# Printrhub_Rev_0_1.net
KiCad netlist of a schematic drawn in EAGLE
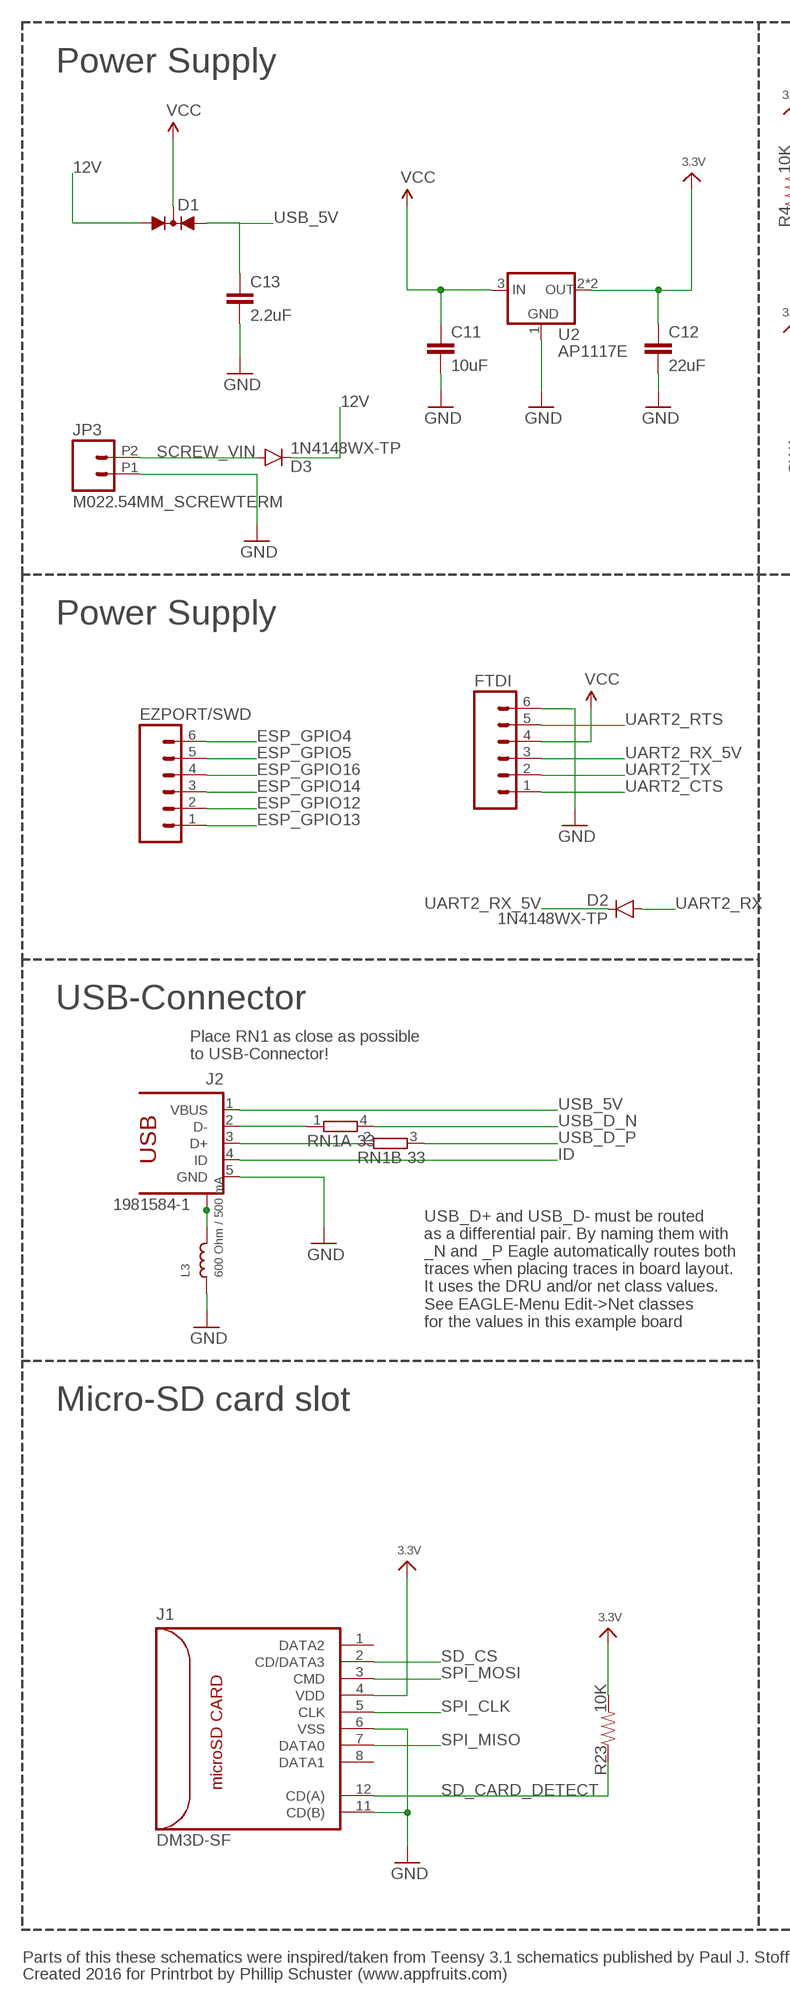
[diagram p0: schematic, sheet 1, part 1 of 2]
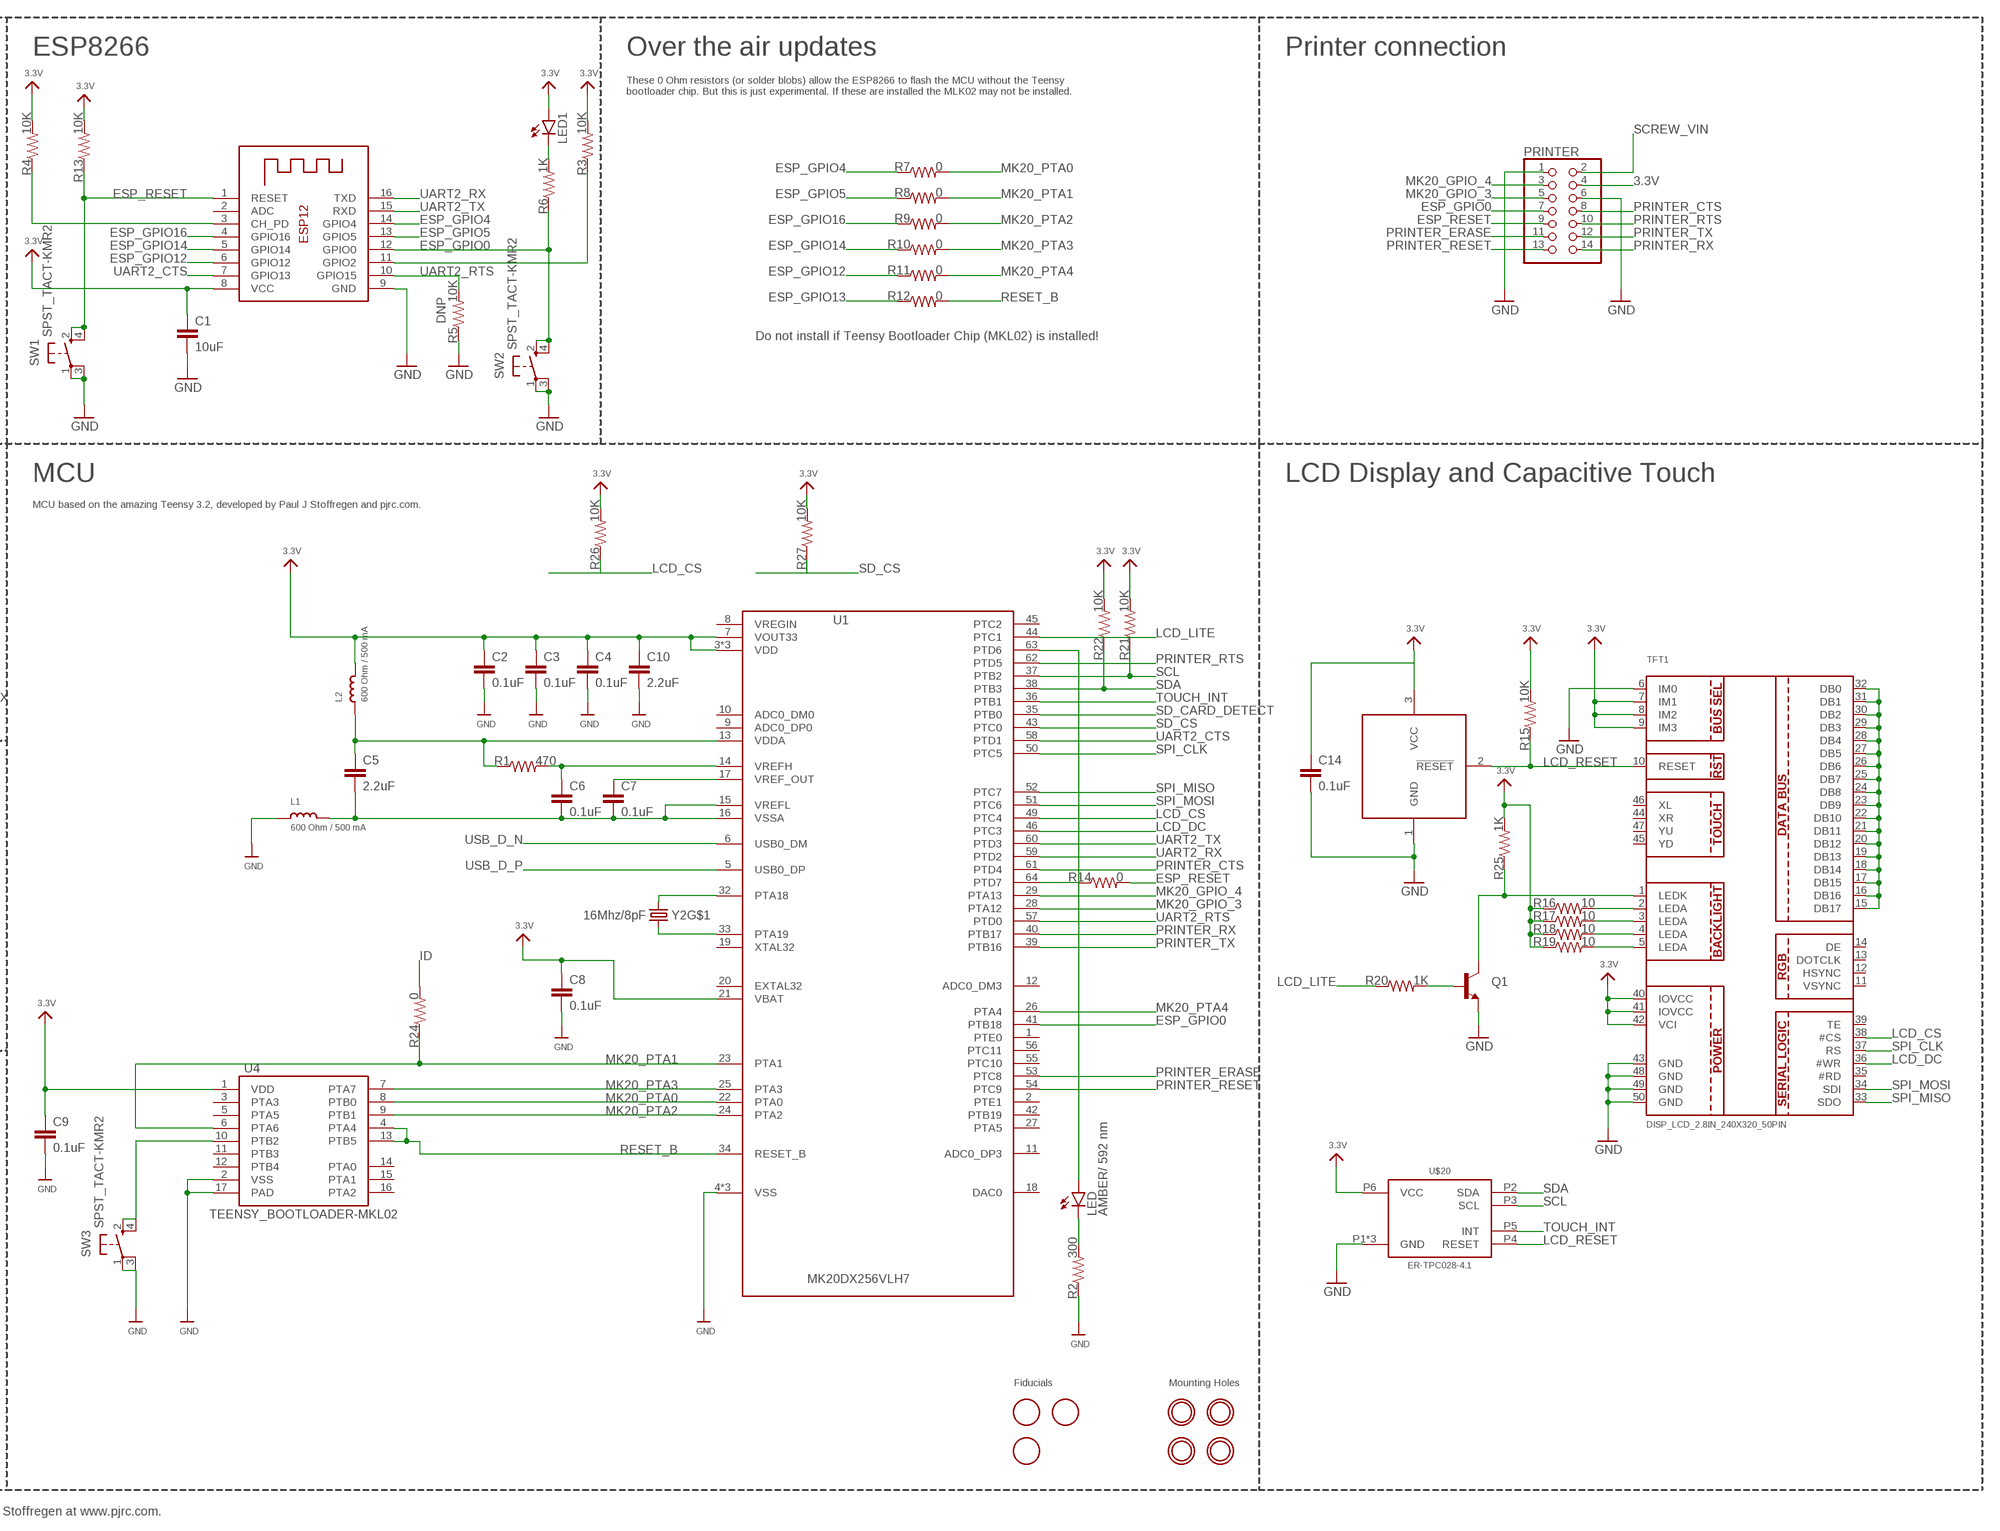
[diagram p1: schematic, sheet 1, part 2 of 2]

(export (version "E")
  (design (tool "Eeschema 10.0.6"))
  (components
    (comp (ref "C1")
      (value "10uF")
      (footprint "eagle-import:0603-CAP")
      (fields (field (name "MF") "Murata") (field (name "MPN") "GRM188R60J106ME47D"))
      (libsource (lib "eagle-import") (part "CAPACITOR-10UF"))
    )
    (comp (ref "C2")
      (value "0.1uF")
      (footprint "eagle-import:0603-CAP")
      (fields (field (name "MF") "Kemet") (field (name "MPN") "C0603C104J3RACTU"))
      (libsource (lib "eagle-import") (part "CAPACITOR-0.1UF"))
    )
    (comp (ref "C3")
      (value "0.1uF")
      (footprint "eagle-import:0603-CAP")
      (fields (field (name "MF") "Kemet") (field (name "MPN") "C0603C104J3RACTU"))
      (libsource (lib "eagle-import") (part "CAPACITOR-0.1UF"))
    )
    (comp (ref "C4")
      (value "0.1uF")
      (footprint "eagle-import:0603-CAP")
      (fields (field (name "MF") "Kemet") (field (name "MPN") "C0603C104J3RACTU"))
      (libsource (lib "eagle-import") (part "CAPACITOR-0.1UF"))
    )
    (comp (ref "C5")
      (value "2.2uF")
      (footprint "eagle-import:0603-CAP")
      (fields (field (name "MF") "Kemet") (field (name "MPN") "C0603C225K4PACTU"))
      (libsource (lib "eagle-import") (part "CAPACITOR-2.2UF"))
    )
    (comp (ref "C6")
      (value "0.1uF")
      (footprint "eagle-import:0603-CAP")
      (fields (field (name "MF") "Kemet") (field (name "MPN") "C0603C104J3RACTU"))
      (libsource (lib "eagle-import") (part "CAPACITOR-0.1UF"))
    )
    (comp (ref "C7")
      (value "0.1uF")
      (footprint "eagle-import:0603-CAP")
      (fields (field (name "MF") "Kemet") (field (name "MPN") "C0603C104J3RACTU"))
      (libsource (lib "eagle-import") (part "CAPACITOR-0.1UF"))
    )
    (comp (ref "C8")
      (value "0.1uF")
      (footprint "eagle-import:0603-CAP")
      (fields (field (name "MF") "Kemet") (field (name "MPN") "C0603C104J3RACTU"))
      (libsource (lib "eagle-import") (part "CAPACITOR-0.1UF"))
    )
    (comp (ref "C9")
      (value "0.1uF")
      (footprint "eagle-import:0603-CAP")
      (fields (field (name "MF") "Kemet") (field (name "MPN") "C0603C104J3RACTU"))
      (libsource (lib "eagle-import") (part "CAPACITOR-0.1UF"))
    )
    (comp (ref "C10")
      (value "2.2uF")
      (footprint "eagle-import:0603-CAP")
      (fields (field (name "MF") "Kemet") (field (name "MPN") "C0603C225K4PACTU"))
      (libsource (lib "eagle-import") (part "CAPACITOR-2.2UF"))
    )
    (comp (ref "C11")
      (value "10uF")
      (footprint "eagle-import:0603-CAP")
      (fields (field (name "MF") "Murata") (field (name "MPN") "GRM188R60J106ME47D"))
      (libsource (lib "eagle-import") (part "CAPACITOR-10UF"))
    )
    (comp (ref "C12")
      (value "22uF")
      (footprint "eagle-import:0603-CAP")
      (fields (field (name "MF") "Murata") (field (name "MPN") "GRM188R60J226MEA0D"))
      (libsource (lib "eagle-import") (part "CAPACITOR-22UF"))
    )
    (comp (ref "C13")
      (value "2.2uF")
      (footprint "eagle-import:0603-CAP")
      (fields (field (name "MF") "Kemet") (field (name "MPN") "C0603C225K4PACTU"))
      (libsource (lib "eagle-import") (part "CAPACITOR-2.2UF"))
    )
    (comp (ref "C14")
      (value "0.1uF")
      (footprint "eagle-import:0603-CAP")
      (fields (field (name "MF") "Kemet") (field (name "MPN") "C0603C104J3RACTU"))
      (libsource (lib "eagle-import") (part "CAPACITOR-0.1UF"))
    )
    (comp (ref "D1")
      (value "DIODE-2AC|CASOT23")
      (footprint "eagle-import:SOT23")
      (libsource (lib "eagle-import") (part "DIODE-2AC|CASOT23"))
    )
    (comp (ref "D2")
      (value "1N4148WX-TP")
      (footprint "eagle-import:SOD-323")
      (fields (field (name "MF") "Micro Commercial Co"))
      (libsource (lib "eagle-import") (part "DIODESOD"))
    )
    (comp (ref "D3")
      (value "1N4148WX-TP")
      (footprint "eagle-import:SOD-323")
      (fields (field (name "MF") "Micro Commercial Co"))
      (libsource (lib "eagle-import") (part "DIODESOD"))
    )
    (comp (ref "EZPORT/SWD")
      (value "M06SMD-STRAIGHT")
      (footprint "eagle-import:1X06_SMD_STRAIGHT")
      (libsource (lib "eagle-import") (part "M06SMD-STRAIGHT"))
    )
    (comp (ref "FTDI")
      (value "M06SMD-STRAIGHT")
      (footprint "eagle-import:1X06_SMD_STRAIGHT")
      (libsource (lib "eagle-import") (part "M06SMD-STRAIGHT"))
    )
    (comp (ref "J1")
      (value "DM3D-SF")
      (footprint "eagle-import:DM3D-SF")
      (libsource (lib "eagle-import") (part "DM3D-SF"))
    )
    (comp (ref "J2")
      (value "1981584-1")
      (footprint "eagle-import:1981584-1")
      (libsource (lib "eagle-import") (part "1981584-1"))
    )
    (comp (ref "JP3")
      (value "M022.54MM_SCREWTERM")
      (footprint "eagle-import:1X02_2.54_SCREWTERM")
      (libsource (lib "eagle-import") (part "M022.54MM_SCREWTERM"))
    )
    (comp (ref "L1")
      (value "600 Ohm / 500 mA")
      (footprint "eagle-import:0603")
      (fields (field (name "MF") "Murata") (field (name "MPN") "BLM18AG601SN1D"))
      (libsource (lib "eagle-import") (part "INDUCTOR-0603_600OHM/500MA"))
    )
    (comp (ref "L2")
      (value "600 Ohm / 500 mA")
      (footprint "eagle-import:0603")
      (fields (field (name "MF") "Murata") (field (name "MPN") "BLM18AG601SN1D"))
      (libsource (lib "eagle-import") (part "INDUCTOR-0603_600OHM/500MA"))
    )
    (comp (ref "L3")
      (value "600 Ohm / 500 mA")
      (footprint "eagle-import:0603")
      (fields (field (name "MF") "Murata") (field (name "MPN") "BLM18AG601SN1D"))
      (libsource (lib "eagle-import") (part "INDUCTOR-0603_600OHM/500MA"))
    )
    (comp (ref "LED")
      (value "AMBER/ 592 nm")
      (footprint "eagle-import:LED-0603")
      (fields (field (name "MF") "Avago Technologies") (field (name "MPN") "HSMA-C190"))
      (libsource (lib "eagle-import") (part "LED-AMBER"))
    )
    (comp (ref "LED1")
      (value "LED-GREEN")
      (footprint "eagle-import:LED-0603")
      (fields (field (name "MF") "Avago") (field (name "MPN") "HSMG-C190"))
      (libsource (lib "eagle-import") (part "LED-GREEN"))
    )
    (comp (ref "PRINTER")
      (value "PINHD-2X7SMT")
      (footprint "eagle-import:2X07_SMT")
      (libsource (lib "eagle-import") (part "PINHD-2X7SMT"))
    )
    (comp (ref "Q1")
      (value "TRANSISTOR_NPNSOT23-3")
      (footprint "eagle-import:SOT23-3")
      (fields (field (name "MF") "ON Semiconductor") (field (name "MPN") "MMBT2222ALT1G"))
      (libsource (lib "eagle-import") (part "TRANSISTOR_NPNSOT23-3"))
    )
    (comp (ref "R1")
      (value "470")
      (footprint "eagle-import:0603-RES")
      (fields (field (name "MF") "Panasonic") (field (name "MPN") "ERJ-3GEYJ471V"))
      (libsource (lib "eagle-import") (part "RESISTOR-470"))
    )
    (comp (ref "R2")
      (value "300")
      (footprint "eagle-import:0603-RES")
      (libsource (lib "eagle-import") (part "RESISTOR0603"))
    )
    (comp (ref "R3")
      (value "10K")
      (footprint "eagle-import:0603-RES")
      (fields (field (name "MF") "Panasonic") (field (name "MPN") "ERJ-3GEYJ103V"))
      (libsource (lib "eagle-import") (part "RESISTOR-10K"))
    )
    (comp (ref "R4")
      (value "10K")
      (footprint "eagle-import:0603-RES")
      (fields (field (name "MF") "Panasonic") (field (name "MPN") "ERJ-3GEYJ103V"))
      (libsource (lib "eagle-import") (part "RESISTOR-10K"))
    )
    (comp (ref "R5")
      (value "10K")
      (footprint "eagle-import:0603-RES")
      (fields (field (name "MF") "Panasonic") (field (name "MPN") "ERJ-3GEYJ103V"))
      (libsource (lib "eagle-import") (part "RESISTOR-10K"))
    )
    (comp (ref "R6")
      (value "1K")
      (footprint "eagle-import:0603-RES")
      (fields (field (name "MF") "Panasonic") (field (name "MPN") "ERJ-3GEYJ102V"))
      (libsource (lib "eagle-import") (part "RESISTOR-1K"))
    )
    (comp (ref "R7")
      (value "0")
      (footprint "eagle-import:0603-RES")
      (fields (field (name "MF") "Panasonic") (field (name "MPN") "ERJ-3GEY0R00V"))
      (libsource (lib "eagle-import") (part "RESISTOR-0"))
    )
    (comp (ref "R8")
      (value "0")
      (footprint "eagle-import:0603-RES")
      (fields (field (name "MF") "Panasonic") (field (name "MPN") "ERJ-3GEY0R00V"))
      (libsource (lib "eagle-import") (part "RESISTOR-0"))
    )
    (comp (ref "R9")
      (value "0")
      (footprint "eagle-import:0603-RES")
      (fields (field (name "MF") "Panasonic") (field (name "MPN") "ERJ-3GEY0R00V"))
      (libsource (lib "eagle-import") (part "RESISTOR-0"))
    )
    (comp (ref "R10")
      (value "0")
      (footprint "eagle-import:0603-RES")
      (fields (field (name "MF") "Panasonic") (field (name "MPN") "ERJ-3GEY0R00V"))
      (libsource (lib "eagle-import") (part "RESISTOR-0"))
    )
    (comp (ref "R11")
      (value "0")
      (footprint "eagle-import:0603-RES")
      (fields (field (name "MF") "Panasonic") (field (name "MPN") "ERJ-3GEY0R00V"))
      (libsource (lib "eagle-import") (part "RESISTOR-0"))
    )
    (comp (ref "R12")
      (value "0")
      (footprint "eagle-import:0603-RES")
      (fields (field (name "MF") "Panasonic") (field (name "MPN") "ERJ-3GEY0R00V"))
      (libsource (lib "eagle-import") (part "RESISTOR-0"))
    )
    (comp (ref "R13")
      (value "10K")
      (footprint "eagle-import:0603-RES")
      (fields (field (name "MF") "Panasonic") (field (name "MPN") "ERJ-3GEYJ103V"))
      (libsource (lib "eagle-import") (part "RESISTOR-10K"))
    )
    (comp (ref "R14")
      (value "0")
      (footprint "eagle-import:0603-RES")
      (fields (field (name "MF") "Panasonic") (field (name "MPN") "ERJ-3GEY0R00V"))
      (libsource (lib "eagle-import") (part "RESISTOR-0"))
    )
    (comp (ref "R15")
      (value "10K")
      (footprint "eagle-import:0603-RES")
      (fields (field (name "MF") "Panasonic") (field (name "MPN") "ERJ-3GEYJ103V"))
      (libsource (lib "eagle-import") (part "RESISTOR-10K"))
    )
    (comp (ref "R16")
      (value "10")
      (footprint "eagle-import:0603-RES")
      (fields (field (name "MF") "Panasonic") (field (name "MPN") "ERJ-3EKF10R0V"))
      (libsource (lib "eagle-import") (part "RESISTOR-10"))
    )
    (comp (ref "R17")
      (value "10")
      (footprint "eagle-import:0603-RES")
      (fields (field (name "MF") "Panasonic") (field (name "MPN") "ERJ-3EKF10R0V"))
      (libsource (lib "eagle-import") (part "RESISTOR-10"))
    )
    (comp (ref "R18")
      (value "10")
      (footprint "eagle-import:0603-RES")
      (fields (field (name "MF") "Panasonic") (field (name "MPN") "ERJ-3EKF10R0V"))
      (libsource (lib "eagle-import") (part "RESISTOR-10"))
    )
    (comp (ref "R19")
      (value "10")
      (footprint "eagle-import:0603-RES")
      (fields (field (name "MF") "Panasonic") (field (name "MPN") "ERJ-3EKF10R0V"))
      (libsource (lib "eagle-import") (part "RESISTOR-10"))
    )
    (comp (ref "R20")
      (value "1K")
      (footprint "eagle-import:0603-RES")
      (fields (field (name "MF") "Panasonic") (field (name "MPN") "ERJ-3GEYJ102V"))
      (libsource (lib "eagle-import") (part "RESISTOR-1K"))
    )
    (comp (ref "R21")
      (value "10K")
      (footprint "eagle-import:0603-RES")
      (fields (field (name "MF") "Panasonic") (field (name "MPN") "ERJ-3GEYJ103V"))
      (libsource (lib "eagle-import") (part "RESISTOR-10K"))
    )
    (comp (ref "R22")
      (value "10K")
      (footprint "eagle-import:0603-RES")
      (fields (field (name "MF") "Panasonic") (field (name "MPN") "ERJ-3GEYJ103V"))
      (libsource (lib "eagle-import") (part "RESISTOR-10K"))
    )
    (comp (ref "R23")
      (value "10K")
      (footprint "eagle-import:0603-RES")
      (fields (field (name "MF") "Panasonic") (field (name "MPN") "ERJ-3GEYJ103V"))
      (libsource (lib "eagle-import") (part "RESISTOR-10K"))
    )
    (comp (ref "R24")
      (value "0")
      (footprint "eagle-import:0603-RES")
      (fields (field (name "MF") "Panasonic") (field (name "MPN") "ERJ-3GEY0R00V"))
      (libsource (lib "eagle-import") (part "RESISTOR-0"))
    )
    (comp (ref "R25")
      (value "1K")
      (footprint "eagle-import:0603-RES")
      (fields (field (name "MF") "Panasonic") (field (name "MPN") "ERJ-3GEYJ102V"))
      (libsource (lib "eagle-import") (part "RESISTOR-1K"))
    )
    (comp (ref "R26")
      (value "10K")
      (footprint "eagle-import:0603-RES")
      (fields (field (name "MF") "Panasonic") (field (name "MPN") "ERJ-3GEYJ103V"))
      (libsource (lib "eagle-import") (part "RESISTOR-10K"))
    )
    (comp (ref "R27")
      (value "10K")
      (footprint "eagle-import:0603-RES")
      (fields (field (name "MF") "Panasonic") (field (name "MPN") "ERJ-3GEYJ103V"))
      (libsource (lib "eagle-import") (part "RESISTOR-10K"))
    )
    (comp (ref "RN1")
      (value "33")
      (footprint "eagle-import:EXB34V")
      (fields (field (name "MF") "Panasonic") (field (name "MPN") "EXB-34V330JV"))
      (libsource (lib "eagle-import") (part "2R-NEXB34V"))
    )
    (comp (ref "SW1")
      (value "SPST_TACT-KMR2")
      (footprint "eagle-import:KMR2")
      (libsource (lib "eagle-import") (part "SPST_TACT-KMR2"))
    )
    (comp (ref "SW2")
      (value "SPST_TACT-KMR2")
      (footprint "eagle-import:KMR2")
      (libsource (lib "eagle-import") (part "SPST_TACT-KMR2"))
    )
    (comp (ref "SW3")
      (value "SPST_TACT-KMR2")
      (footprint "eagle-import:KMR2")
      (libsource (lib "eagle-import") (part "SPST_TACT-KMR2"))
    )
    (comp (ref "TFT1")
      (value "DISP_LCD_2.8IN_240X320_50PIN")
      (footprint "eagle-import:TFT_2.83IN_240X320_50PIN")
      (libsource (lib "eagle-import") (part "DISP_LCD_2.8IN_240X320_50PIN"))
    )
    (comp (ref "U$15")
      (value "MOUNTINGHOLE2.0")
      (footprint "eagle-import:MOUNTINGHOLE_2.0_PLATED")
      (libsource (lib "eagle-import") (part "MOUNTINGHOLE2.0"))
    )
    (comp (ref "U$16")
      (value "MOUNTINGHOLE2.0")
      (footprint "eagle-import:MOUNTINGHOLE_2.0_PLATED")
      (libsource (lib "eagle-import") (part "MOUNTINGHOLE2.0"))
    )
    (comp (ref "U$17")
      (value "MOUNTINGHOLE2.0")
      (footprint "eagle-import:MOUNTINGHOLE_2.0_PLATED")
      (libsource (lib "eagle-import") (part "MOUNTINGHOLE2.0"))
    )
    (comp (ref "U$18")
      (value "MOUNTINGHOLE2.0")
      (footprint "eagle-import:MOUNTINGHOLE_2.0_PLATED")
      (libsource (lib "eagle-import") (part "MOUNTINGHOLE2.0"))
    )
    (comp (ref "U$20")
      (value "ER-TPC028-4.1")
      (footprint "eagle-import:ER-CON06HB-1")
      (libsource (lib "eagle-import") (part "ER-TPC028-4.1"))
    )
    (comp (ref "U$38")
      (value "FIDUCIAL")
      (footprint "eagle-import:FIDUCIAL_1MM")
      (libsource (lib "eagle-import") (part "FIDUCIAL"))
    )
    (comp (ref "U$39")
      (value "FIDUCIAL")
      (footprint "eagle-import:FIDUCIAL_1MM")
      (libsource (lib "eagle-import") (part "FIDUCIAL"))
    )
    (comp (ref "U$40")
      (value "FIDUCIAL")
      (footprint "eagle-import:FIDUCIAL_1MM")
      (libsource (lib "eagle-import") (part "FIDUCIAL"))
    )
    (comp (ref "U1")
      (value "MK20DX256VLH7")
      (footprint "eagle-import:MK20DX256VLH7")
      (fields (field (name "MF") "Freescale"))
      (libsource (lib "eagle-import") (part "MK20DX256VLH7"))
    )
    (comp (ref "U2")
      (value "AP1117E")
      (footprint "eagle-import:SOT223")
      (libsource (lib "eagle-import") (part "AP1117E"))
    )
    (comp (ref "U3")
      (value "MAX308-SOT23")
      (footprint "eagle-import:SOT23")
      (libsource (lib "eagle-import") (part "MAX308-SOT23"))
    )
    (comp (ref "U4")
      (value "TEENSY_BOOTLOADER-MKL02")
      (footprint "eagle-import:QFN50P300X300X100-17N")
      (libsource (lib "eagle-import") (part "TEENSY_BOOTLOADER-MKL02"))
    )
    (comp (ref "X1")
      (value "ESP-12")
      (footprint "eagle-import:ESP-12")
      (libsource (lib "eagle-import") (part "ESP-12"))
    )
    (comp (ref "Y2")
      (value "16Mhz/8pF")
      (footprint "eagle-import:CRYSTAL-SMD-5X3")
      (fields (field (name "MF") "ECS") (field (name "MPN") "ECS-160-8-30B-CKM"))
      (libsource (lib "eagle-import") (part "CRYSTAL/SMD-5X3-GND16MHZ/8PF"))
    )
  )
  (nets
    (net (code "1") (name "/12V") (class "Default")
      (node (ref "D1") (pin "1") (pinfunction "A1_1") (pintype "passive"))
      (node (ref "D3") (pin "C") (pinfunction "C_C") (pintype "passive"))
    )
    (net (code "2") (name "/ESP_GPIO0") (class "Default")
      (node (ref "PRINTER") (pin "7") (pinfunction "7_7") (pintype "passive"))
      (node (ref "R6") (pin "1") (pinfunction "1_1") (pintype "passive"))
      (node (ref "SW2") (pin "2") (pinfunction "S_2") (pintype "passive"))
      (node (ref "SW2") (pin "4") (pinfunction "S1_4") (pintype "passive"))
      (node (ref "U1") (pin "41") (pinfunction "PTB18_41") (pintype "bidirectional"))
      (node (ref "X1") (pin "12") (pinfunction "GPIO0_12") (pintype "bidirectional"))
    )
    (net (code "3") (name "/ESP_GPIO4") (class "Default")
      (node (ref "EZPORT/SWD") (pin "6") (pinfunction "6_6") (pintype "passive"))
      (node (ref "R7") (pin "1") (pinfunction "1_1") (pintype "passive"))
      (node (ref "X1") (pin "14") (pinfunction "GPIO4_14") (pintype "bidirectional"))
    )
    (net (code "4") (name "/ESP_GPIO5") (class "Default")
      (node (ref "EZPORT/SWD") (pin "5") (pinfunction "5_5") (pintype "passive"))
      (node (ref "R8") (pin "1") (pinfunction "1_1") (pintype "passive"))
      (node (ref "X1") (pin "13") (pinfunction "GPIO5_13") (pintype "bidirectional"))
    )
    (net (code "5") (name "/ESP_GPIO12") (class "Default")
      (node (ref "EZPORT/SWD") (pin "2") (pinfunction "2_2") (pintype "passive"))
      (node (ref "R11") (pin "1") (pinfunction "1_1") (pintype "passive"))
      (node (ref "X1") (pin "6") (pinfunction "GPIO12_6") (pintype "bidirectional"))
    )
    (net (code "6") (name "/ESP_GPIO13") (class "Default")
      (node (ref "EZPORT/SWD") (pin "1") (pinfunction "1_1") (pintype "passive"))
      (node (ref "R12") (pin "1") (pinfunction "1_1") (pintype "passive"))
    )
    (net (code "7") (name "/ESP_GPIO14") (class "Default")
      (node (ref "EZPORT/SWD") (pin "3") (pinfunction "3_3") (pintype "passive"))
      (node (ref "R10") (pin "1") (pinfunction "1_1") (pintype "passive"))
      (node (ref "X1") (pin "5") (pinfunction "GPIO14_5") (pintype "bidirectional"))
    )
    (net (code "8") (name "/ESP_GPIO16") (class "Default")
      (node (ref "EZPORT/SWD") (pin "4") (pinfunction "4_4") (pintype "passive"))
      (node (ref "R9") (pin "1") (pinfunction "1_1") (pintype "passive"))
      (node (ref "X1") (pin "4") (pinfunction "GPIO16_4") (pintype "bidirectional"))
    )
    (net (code "9") (name "/ESP_RESET") (class "Default")
      (node (ref "PRINTER") (pin "9") (pinfunction "9_9") (pintype "passive"))
      (node (ref "R13") (pin "1") (pinfunction "1_1") (pintype "passive"))
      (node (ref "R14") (pin "2") (pinfunction "2_2") (pintype "passive"))
      (node (ref "SW1") (pin "2") (pinfunction "S_2") (pintype "passive"))
      (node (ref "SW1") (pin "4") (pinfunction "S1_4") (pintype "passive"))
      (node (ref "X1") (pin "1") (pinfunction "RESET_1") (pintype "input"))
    )
    (net (code "10") (name "/ID") (class "Default")
      (node (ref "J2") (pin "4") (pinfunction "ID_4") (pintype "passive"))
      (node (ref "R24") (pin "2") (pinfunction "2_2") (pintype "passive"))
    )
    (net (code "11") (name "/LCD_CS") (class "Default")
      (node (ref "R26") (pin "1") (pinfunction "1_1") (pintype "passive"))
      (node (ref "TFT1") (pin "38") (pinfunction "#CS_38") (pintype "bidirectional"))
      (node (ref "U1") (pin "49") (pinfunction "PTC4_49") (pintype "bidirectional"))
    )
    (net (code "12") (name "/LCD_DC") (class "Default")
      (node (ref "TFT1") (pin "36") (pinfunction "#WR_36") (pintype "bidirectional"))
      (node (ref "U1") (pin "46") (pinfunction "PTC3_46") (pintype "bidirectional"))
    )
    (net (code "13") (name "/LCD_LITE") (class "Default")
      (node (ref "R20") (pin "1") (pinfunction "1_1") (pintype "passive"))
      (node (ref "U1") (pin "44") (pinfunction "PTC1_44") (pintype "bidirectional"))
    )
    (net (code "14") (name "/LCD_RESET") (class "Default")
      (node (ref "R15") (pin "1") (pinfunction "1_1") (pintype "passive"))
      (node (ref "TFT1") (pin "10") (pinfunction "RESET_10") (pintype "bidirectional"))
      (node (ref "U$20") (pin "P4") (pinfunction "RESET_P4") (pintype "bidirectional"))
      (node (ref "U3") (pin "2") (pinfunction "~{RESET}_2") (pintype "bidirectional"))
    )
    (net (code "15") (name "/MK20_GPIO_3") (class "Default")
      (node (ref "PRINTER") (pin "5") (pinfunction "5_5") (pintype "passive"))
      (node (ref "U1") (pin "28") (pinfunction "PTA12_28") (pintype "bidirectional"))
    )
    (net (code "16") (name "/MK20_GPIO_4") (class "Default")
      (node (ref "PRINTER") (pin "3") (pinfunction "3_3") (pintype "passive"))
      (node (ref "U1") (pin "29") (pinfunction "PTA13_29") (pintype "bidirectional"))
    )
    (net (code "17") (name "/MK20_PTA0") (class "Default")
      (node (ref "R7") (pin "2") (pinfunction "2_2") (pintype "passive"))
      (node (ref "U1") (pin "22") (pinfunction "PTA0_22") (pintype "bidirectional"))
      (node (ref "U4") (pin "8") (pinfunction "PTB0_8") (pintype "bidirectional"))
    )
    (net (code "18") (name "/MK20_PTA1") (class "Default")
      (node (ref "R24") (pin "1") (pinfunction "1_1") (pintype "passive"))
      (node (ref "R8") (pin "2") (pinfunction "2_2") (pintype "passive"))
      (node (ref "U1") (pin "23") (pinfunction "PTA1_23") (pintype "bidirectional"))
      (node (ref "U4") (pin "6") (pinfunction "PTA6_6") (pintype "bidirectional"))
    )
    (net (code "19") (name "/MK20_PTA2") (class "Default")
      (node (ref "R9") (pin "2") (pinfunction "2_2") (pintype "passive"))
      (node (ref "U1") (pin "24") (pinfunction "PTA2_24") (pintype "bidirectional"))
      (node (ref "U4") (pin "9") (pinfunction "PTB1_9") (pintype "bidirectional"))
    )
    (net (code "20") (name "/MK20_PTA3") (class "Default")
      (node (ref "R10") (pin "2") (pinfunction "2_2") (pintype "passive"))
      (node (ref "U1") (pin "25") (pinfunction "PTA3_25") (pintype "bidirectional"))
      (node (ref "U4") (pin "7") (pinfunction "PTA7_7") (pintype "bidirectional"))
    )
    (net (code "21") (name "/MK20_PTA4") (class "Default")
      (node (ref "R11") (pin "2") (pinfunction "2_2") (pintype "passive"))
      (node (ref "U1") (pin "26") (pinfunction "PTA4_26") (pintype "bidirectional"))
    )
    (net (code "22") (name "/PRINTER_CTS") (class "Default")
      (node (ref "PRINTER") (pin "8") (pinfunction "8_8") (pintype "passive"))
      (node (ref "U1") (pin "61") (pinfunction "PTD4_61") (pintype "bidirectional"))
    )
    (net (code "23") (name "/PRINTER_ERASE") (class "Default")
      (node (ref "PRINTER") (pin "11") (pinfunction "11_11") (pintype "passive"))
      (node (ref "U1") (pin "53") (pinfunction "PTC8_53") (pintype "bidirectional"))
    )
    (net (code "24") (name "/PRINTER_RESET") (class "Default")
      (node (ref "PRINTER") (pin "13") (pinfunction "13_13") (pintype "passive"))
      (node (ref "U1") (pin "54") (pinfunction "PTC9_54") (pintype "bidirectional"))
    )
    (net (code "25") (name "/PRINTER_RTS") (class "Default")
      (node (ref "PRINTER") (pin "10") (pinfunction "10_10") (pintype "passive"))
      (node (ref "U1") (pin "62") (pinfunction "PTD5_62") (pintype "bidirectional"))
    )
    (net (code "26") (name "/PRINTER_RX") (class "Default")
      (node (ref "PRINTER") (pin "14") (pinfunction "14_14") (pintype "passive"))
      (node (ref "U1") (pin "40") (pinfunction "PTB17_40") (pintype "bidirectional"))
    )
    (net (code "27") (name "/PRINTER_TX") (class "Default")
      (node (ref "PRINTER") (pin "12") (pinfunction "12_12") (pintype "passive"))
      (node (ref "U1") (pin "39") (pinfunction "PTB16_39") (pintype "bidirectional"))
    )
    (net (code "28") (name "/RESET_B") (class "Default")
      (node (ref "R12") (pin "2") (pinfunction "2_2") (pintype "passive"))
      (node (ref "U1") (pin "34") (pinfunction "RESET_B_34") (pintype "bidirectional"))
      (node (ref "U4") (pin "13") (pinfunction "PTB5_13") (pintype "bidirectional"))
      (node (ref "U4") (pin "4") (pinfunction "PTA4_4") (pintype "bidirectional"))
    )
    (net (code "29") (name "/SCL") (class "Default")
      (node (ref "R21") (pin "1") (pinfunction "1_1") (pintype "passive"))
      (node (ref "U$20") (pin "P3") (pinfunction "SCL_P3") (pintype "bidirectional"))
      (node (ref "U1") (pin "37") (pinfunction "PTB2_37") (pintype "bidirectional"))
    )
    (net (code "30") (name "/SCREW_VIN") (class "Default")
      (node (ref "D3") (pin "A") (pinfunction "A_A") (pintype "passive"))
      (node (ref "JP3") (pin "P2") (pinfunction "2_P2") (pintype "passive"))
      (node (ref "PRINTER") (pin "2") (pinfunction "2_2") (pintype "passive"))
    )
    (net (code "31") (name "/SDA") (class "Default")
      (node (ref "R22") (pin "1") (pinfunction "1_1") (pintype "passive"))
      (node (ref "U$20") (pin "P2") (pinfunction "SDA_P2") (pintype "bidirectional"))
      (node (ref "U1") (pin "38") (pinfunction "PTB3_38") (pintype "bidirectional"))
    )
    (net (code "32") (name "/SD_CARD_DETECT") (class "Default")
      (node (ref "J1") (pin "12") (pinfunction "CD(A)_12") (pintype "bidirectional"))
      (node (ref "R23") (pin "1") (pinfunction "1_1") (pintype "passive"))
      (node (ref "U1") (pin "35") (pinfunction "PTB0_35") (pintype "bidirectional"))
    )
    (net (code "33") (name "/SD_CS") (class "Default")
      (node (ref "J1") (pin "2") (pinfunction "CD/DATA3_2") (pintype "bidirectional"))
      (node (ref "R27") (pin "1") (pinfunction "1_1") (pintype "passive"))
      (node (ref "U1") (pin "43") (pinfunction "PTC0_43") (pintype "bidirectional"))
    )
    (net (code "34") (name "/SPI_CLK") (class "Default")
      (node (ref "J1") (pin "5") (pinfunction "CLK_5") (pintype "bidirectional"))
      (node (ref "TFT1") (pin "37") (pinfunction "RS_37") (pintype "bidirectional"))
      (node (ref "U1") (pin "50") (pinfunction "PTC5_50") (pintype "bidirectional"))
    )
    (net (code "35") (name "/SPI_MISO") (class "Default")
      (node (ref "J1") (pin "7") (pinfunction "DATA0_7") (pintype "bidirectional"))
      (node (ref "TFT1") (pin "33") (pinfunction "SDO_33") (pintype "bidirectional"))
      (node (ref "U1") (pin "52") (pinfunction "PTC7_52") (pintype "bidirectional"))
    )
    (net (code "36") (name "/SPI_MOSI") (class "Default")
      (node (ref "J1") (pin "3") (pinfunction "CMD_3") (pintype "bidirectional"))
      (node (ref "TFT1") (pin "34") (pinfunction "SDI_34") (pintype "bidirectional"))
      (node (ref "U1") (pin "51") (pinfunction "PTC6_51") (pintype "bidirectional"))
    )
    (net (code "37") (name "/TOUCH_INT") (class "Default")
      (node (ref "U$20") (pin "P5") (pinfunction "INT_P5") (pintype "bidirectional"))
      (node (ref "U1") (pin "36") (pinfunction "PTB1_36") (pintype "bidirectional"))
    )
    (net (code "38") (name "/UART2_CTS") (class "Default")
      (node (ref "FTDI") (pin "1") (pinfunction "1_1") (pintype "passive"))
      (node (ref "U1") (pin "58") (pinfunction "PTD1_58") (pintype "bidirectional"))
      (node (ref "X1") (pin "7") (pinfunction "GPIO13_7") (pintype "bidirectional"))
    )
    (net (code "39") (name "/UART2_RTS") (class "Default")
      (node (ref "FTDI") (pin "5") (pinfunction "5_5") (pintype "passive"))
      (node (ref "R5") (pin "2") (pinfunction "2_2") (pintype "passive"))
      (node (ref "U1") (pin "57") (pinfunction "PTD0_57") (pintype "bidirectional"))
      (node (ref "X1") (pin "10") (pinfunction "GPIO15_10") (pintype "bidirectional"))
    )
    (net (code "40") (name "/UART2_RX") (class "Default")
      (node (ref "D2") (pin "A") (pinfunction "A_A") (pintype "passive"))
      (node (ref "U1") (pin "59") (pinfunction "PTD2_59") (pintype "bidirectional"))
      (node (ref "X1") (pin "16") (pinfunction "TXD_16") (pintype "output"))
    )
    (net (code "41") (name "/UART2_RX_5V") (class "Default")
      (node (ref "D2") (pin "C") (pinfunction "C_C") (pintype "passive"))
      (node (ref "FTDI") (pin "3") (pinfunction "3_3") (pintype "passive"))
    )
    (net (code "42") (name "/UART2_TX") (class "Default")
      (node (ref "FTDI") (pin "2") (pinfunction "2_2") (pintype "passive"))
      (node (ref "U1") (pin "60") (pinfunction "PTD3_60") (pintype "bidirectional"))
      (node (ref "X1") (pin "15") (pinfunction "RXD_15") (pintype "input"))
    )
    (net (code "43") (name "/USB_5V") (class "Default")
      (node (ref "C13") (pin "1") (pinfunction "1_1") (pintype "passive"))
      (node (ref "D1") (pin "2") (pinfunction "A2_2") (pintype "passive"))
      (node (ref "J2") (pin "1") (pinfunction "VBUS_1") (pintype "passive"))
    )
    (net (code "44") (name "/USB_D_N") (class "Default")
      (node (ref "RN1") (pin "4") (pinfunction "2_4") (pintype "passive"))
      (node (ref "U1") (pin "6") (pinfunction "USB0_DM_6") (pintype "bidirectional"))
    )
    (net (code "45") (name "/USB_D_P") (class "Default")
      (node (ref "RN1") (pin "3") (pinfunction "2_3") (pintype "passive"))
      (node (ref "U1") (pin "5") (pinfunction "USB0_DP_5") (pintype "bidirectional"))
    )
    (net (code "46") (name "3.3V") (class "Default")
      (node (ref "C1") (pin "1") (pinfunction "1_1") (pintype "passive"))
      (node (ref "C10") (pin "1") (pinfunction "1_1") (pintype "passive"))
      (node (ref "C12") (pin "1") (pinfunction "1_1") (pintype "passive"))
      (node (ref "C14") (pin "1") (pinfunction "1_1") (pintype "passive"))
      (node (ref "C2") (pin "1") (pinfunction "1_1") (pintype "passive"))
      (node (ref "C3") (pin "1") (pinfunction "1_1") (pintype "passive"))
      (node (ref "C4") (pin "1") (pinfunction "1_1") (pintype "passive"))
      (node (ref "C8") (pin "1") (pinfunction "1_1") (pintype "passive"))
      (node (ref "C9") (pin "1") (pinfunction "1_1") (pintype "passive"))
      (node (ref "J1") (pin "4") (pinfunction "VDD_4") (pintype "power_in"))
      (node (ref "L2") (pin "2") (pinfunction "2_2") (pintype "passive"))
      (node (ref "LED1") (pin "A") (pinfunction "A_A") (pintype "passive"))
      (node (ref "PRINTER") (pin "4") (pinfunction "4_4") (pintype "passive"))
      (node (ref "R13") (pin "2") (pinfunction "2_2") (pintype "passive"))
      (node (ref "R15") (pin "2") (pinfunction "2_2") (pintype "passive"))
      (node (ref "R16") (pin "1") (pinfunction "1_1") (pintype "passive"))
      (node (ref "R17") (pin "1") (pinfunction "1_1") (pintype "passive"))
      (node (ref "R18") (pin "1") (pinfunction "1_1") (pintype "passive"))
      (node (ref "R19") (pin "1") (pinfunction "1_1") (pintype "passive"))
      (node (ref "R21") (pin "2") (pinfunction "2_2") (pintype "passive"))
      (node (ref "R22") (pin "2") (pinfunction "2_2") (pintype "passive"))
      (node (ref "R23") (pin "2") (pinfunction "2_2") (pintype "passive"))
      (node (ref "R25") (pin "2") (pinfunction "2_2") (pintype "passive"))
      (node (ref "R26") (pin "2") (pinfunction "2_2") (pintype "passive"))
      (node (ref "R27") (pin "2") (pinfunction "2_2") (pintype "passive"))
      (node (ref "R3") (pin "2") (pinfunction "2_2") (pintype "passive"))
      (node (ref "R4") (pin "2") (pinfunction "2_2") (pintype "passive"))
      (node (ref "TFT1") (pin "40") (pinfunction "IOVCC_40") (pintype "bidirectional"))
      (node (ref "TFT1") (pin "41") (pinfunction "IOVCC_41") (pintype "bidirectional"))
      (node (ref "TFT1") (pin "42") (pinfunction "VCI_42") (pintype "bidirectional"))
      (node (ref "TFT1") (pin "7") (pinfunction "IM1_7") (pintype "bidirectional"))
      (node (ref "TFT1") (pin "8") (pinfunction "IM2_8") (pintype "bidirectional"))
      (node (ref "TFT1") (pin "9") (pinfunction "IM3_9") (pintype "bidirectional"))
      (node (ref "U$20") (pin "P6") (pinfunction "VCC_P6") (pintype "bidirectional"))
      (node (ref "U1") (pin "21") (pinfunction "VBAT_21") (pintype "bidirectional"))
      (node (ref "U1") (pin "3") (pinfunction "VDD_3") (pintype "bidirectional"))
      (node (ref "U1") (pin "30") (pinfunction "VDD_30") (pintype "bidirectional"))
      (node (ref "U1") (pin "48") (pinfunction "VDD_48") (pintype "bidirectional"))
      (node (ref "U1") (pin "7") (pinfunction "VOUT33_7") (pintype "bidirectional"))
      (node (ref "U2") (pin "2") (pinfunction "OUT_2") (pintype "passive"))
      (node (ref "U2") (pin "4") (pinfunction "OUT_4") (pintype "passive"))
      (node (ref "U3") (pin "3") (pinfunction "VCC_3") (pintype "bidirectional"))
      (node (ref "U4") (pin "1") (pinfunction "VDD_1") (pintype "power_in"))
      (node (ref "X1") (pin "8") (pinfunction "VCC_8") (pintype "power_in"))
    )
    (net (code "47") (name "GND") (class "Default")
      (node (ref "C1") (pin "2") (pinfunction "2_2") (pintype "passive"))
      (node (ref "C10") (pin "2") (pinfunction "2_2") (pintype "passive"))
      (node (ref "C11") (pin "2") (pinfunction "2_2") (pintype "passive"))
      (node (ref "C12") (pin "2") (pinfunction "2_2") (pintype "passive"))
      (node (ref "C13") (pin "2") (pinfunction "2_2") (pintype "passive"))
      (node (ref "C14") (pin "2") (pinfunction "2_2") (pintype "passive"))
      (node (ref "C2") (pin "2") (pinfunction "2_2") (pintype "passive"))
      (node (ref "C3") (pin "2") (pinfunction "2_2") (pintype "passive"))
      (node (ref "C4") (pin "2") (pinfunction "2_2") (pintype "passive"))
      (node (ref "C8") (pin "2") (pinfunction "2_2") (pintype "passive"))
      (node (ref "C9") (pin "2") (pinfunction "2_2") (pintype "passive"))
      (node (ref "FTDI") (pin "6") (pinfunction "6_6") (pintype "passive"))
      (node (ref "J1") (pin "11") (pinfunction "CD(B)_11") (pintype "bidirectional"))
      (node (ref "J1") (pin "6") (pinfunction "VSS_6") (pintype "power_in"))
      (node (ref "J2") (pin "5") (pinfunction "GND_5") (pintype "passive"))
      (node (ref "JP3") (pin "P1") (pinfunction "1_P1") (pintype "passive"))
      (node (ref "L1") (pin "1") (pinfunction "1_1") (pintype "passive"))
      (node (ref "L3") (pin "1") (pinfunction "1_1") (pintype "passive"))
      (node (ref "PRINTER") (pin "1") (pinfunction "1_1") (pintype "passive"))
      (node (ref "PRINTER") (pin "6") (pinfunction "6_6") (pintype "passive"))
      (node (ref "Q1") (pin "2") (pinfunction "E_2") (pintype "passive"))
      (node (ref "R2") (pin "1") (pinfunction "1_1") (pintype "passive"))
      (node (ref "R5") (pin "1") (pinfunction "1_1") (pintype "passive"))
      (node (ref "SW1") (pin "1") (pinfunction "P_1") (pintype "passive"))
      (node (ref "SW1") (pin "3") (pinfunction "P1_3") (pintype "passive"))
      (node (ref "SW2") (pin "1") (pinfunction "P_1") (pintype "passive"))
      (node (ref "SW2") (pin "3") (pinfunction "P1_3") (pintype "passive"))
      (node (ref "SW3") (pin "1") (pinfunction "P_1") (pintype "passive"))
      (node (ref "SW3") (pin "3") (pinfunction "P1_3") (pintype "passive"))
      (node (ref "TFT1") (pin "43") (pinfunction "GND_43") (pintype "bidirectional"))
      (node (ref "TFT1") (pin "48") (pinfunction "GND_48") (pintype "bidirectional"))
      (node (ref "TFT1") (pin "49") (pinfunction "GND_49") (pintype "bidirectional"))
      (node (ref "TFT1") (pin "50") (pinfunction "GND_50") (pintype "bidirectional"))
      (node (ref "TFT1") (pin "6") (pinfunction "IM0_6") (pintype "bidirectional"))
      (node (ref "U$20") (pin "P1") (pinfunction "GND_P1") (pintype "bidirectional"))
      (node (ref "U$20") (pin "PAD@0") (pinfunction "GND_PAD@0") (pintype "bidirectional"))
      (node (ref "U$20") (pin "PAD@1") (pinfunction "GND_PAD@1") (pintype "bidirectional"))
      (node (ref "U1") (pin "31") (pinfunction "VSS_31") (pintype "bidirectional"))
      (node (ref "U1") (pin "4") (pinfunction "VSS_4") (pintype "bidirectional"))
      (node (ref "U1") (pin "47") (pinfunction "VSS_47") (pintype "bidirectional"))
      (node (ref "U2") (pin "1") (pinfunction "GND_1") (pintype "input"))
      (node (ref "U3") (pin "1") (pinfunction "GND_1") (pintype "bidirectional"))
      (node (ref "U4") (pin "17") (pinfunction "PAD_17") (pintype "bidirectional"))
      (node (ref "U4") (pin "2") (pinfunction "VSS_2") (pintype "bidirectional"))
      (node (ref "X1") (pin "9") (pinfunction "GND_9") (pintype "power_in"))
    )
    (net (code "48") (name "Net-(J2-D+)") (class "Default")
      (node (ref "J2") (pin "3") (pinfunction "D+_3") (pintype "passive"))
      (node (ref "RN1") (pin "2") (pinfunction "1_2") (pintype "passive"))
    )
    (net (code "49") (name "Net-(J2-D-)") (class "Default")
      (node (ref "J2") (pin "2") (pinfunction "D-_2") (pintype "passive"))
      (node (ref "RN1") (pin "1") (pinfunction "1_1") (pintype "passive"))
    )
    (net (code "50") (name "Net-(J2-PadS1)") (class "Default")
      (node (ref "J2") (pin "S1") (pinfunction "S1_S1") (pintype "passive"))
      (node (ref "J2") (pin "S2") (pinfunction "S2_S2") (pintype "passive"))
      (node (ref "J2") (pin "S3") (pinfunction "S3_S3") (pintype "passive"))
      (node (ref "J2") (pin "S4") (pinfunction "S4_S4") (pintype "passive"))
      (node (ref "L3") (pin "2") (pinfunction "2_2") (pintype "passive"))
    )
    (net (code "51") (name "Net-(LED-PadC)") (class "Default")
      (node (ref "LED") (pin "C") (pinfunction "C_C") (pintype "passive"))
      (node (ref "R2") (pin "2") (pinfunction "2_2") (pintype "passive"))
    )
    (net (code "52") (name "Net-(LED1-PadC)") (class "Default")
      (node (ref "LED1") (pin "C") (pinfunction "C_C") (pintype "passive"))
      (node (ref "R6") (pin "2") (pinfunction "2_2") (pintype "passive"))
    )
    (net (code "53") (name "Net-(Q1-B)") (class "Default")
      (node (ref "Q1") (pin "1") (pinfunction "B_1") (pintype "passive"))
      (node (ref "R20") (pin "2") (pinfunction "2_2") (pintype "passive"))
    )
    (net (code "54") (name "Net-(Q1-C)") (class "Default")
      (node (ref "Q1") (pin "3") (pinfunction "C_3") (pintype "passive"))
      (node (ref "R25") (pin "1") (pinfunction "1_1") (pintype "passive"))
      (node (ref "TFT1") (pin "1") (pinfunction "LEDK_1") (pintype "bidirectional"))
    )
    (net (code "55") (name "Net-(R16-Pad2)") (class "Default")
      (node (ref "R16") (pin "2") (pinfunction "2_2") (pintype "passive"))
      (node (ref "TFT1") (pin "2") (pinfunction "LEDA_2") (pintype "bidirectional"))
    )
    (net (code "56") (name "Net-(R17-Pad2)") (class "Default")
      (node (ref "R17") (pin "2") (pinfunction "2_2") (pintype "passive"))
      (node (ref "TFT1") (pin "3") (pinfunction "LEDA_3") (pintype "bidirectional"))
    )
    (net (code "57") (name "Net-(R18-Pad2)") (class "Default")
      (node (ref "R18") (pin "2") (pinfunction "2_2") (pintype "passive"))
      (node (ref "TFT1") (pin "4") (pinfunction "LEDA_4") (pintype "bidirectional"))
    )
    (net (code "58") (name "Net-(R19-Pad2)") (class "Default")
      (node (ref "R19") (pin "2") (pinfunction "2_2") (pintype "passive"))
      (node (ref "TFT1") (pin "5") (pinfunction "LEDA_5") (pintype "bidirectional"))
    )
    (net (code "59") (name "Net-(SW3-S)") (class "Default")
      (node (ref "SW3") (pin "2") (pinfunction "S_2") (pintype "passive"))
      (node (ref "SW3") (pin "4") (pinfunction "S1_4") (pintype "passive"))
      (node (ref "U4") (pin "10") (pinfunction "PTB2_10") (pintype "bidirectional"))
    )
    (net (code "60") (name "Net-(TFT1-DB0)") (class "Default")
      (node (ref "TFT1") (pin "15") (pinfunction "DB17_15") (pintype "bidirectional"))
      (node (ref "TFT1") (pin "16") (pinfunction "DB16_16") (pintype "bidirectional"))
      (node (ref "TFT1") (pin "17") (pinfunction "DB15_17") (pintype "bidirectional"))
      (node (ref "TFT1") (pin "18") (pinfunction "DB14_18") (pintype "bidirectional"))
      (node (ref "TFT1") (pin "19") (pinfunction "DB13_19") (pintype "bidirectional"))
      (node (ref "TFT1") (pin "20") (pinfunction "DB12_20") (pintype "bidirectional"))
      (node (ref "TFT1") (pin "21") (pinfunction "DB11_21") (pintype "bidirectional"))
      (node (ref "TFT1") (pin "22") (pinfunction "DB10_22") (pintype "bidirectional"))
      (node (ref "TFT1") (pin "23") (pinfunction "DB9_23") (pintype "bidirectional"))
      (node (ref "TFT1") (pin "24") (pinfunction "DB8_24") (pintype "bidirectional"))
      (node (ref "TFT1") (pin "25") (pinfunction "DB7_25") (pintype "bidirectional"))
      (node (ref "TFT1") (pin "26") (pinfunction "DB6_26") (pintype "bidirectional"))
      (node (ref "TFT1") (pin "27") (pinfunction "DB5_27") (pintype "bidirectional"))
      (node (ref "TFT1") (pin "28") (pinfunction "DB4_28") (pintype "bidirectional"))
      (node (ref "TFT1") (pin "29") (pinfunction "DB3_29") (pintype "bidirectional"))
      (node (ref "TFT1") (pin "30") (pinfunction "DB2_30") (pintype "bidirectional"))
      (node (ref "TFT1") (pin "31") (pinfunction "DB1_31") (pintype "bidirectional"))
      (node (ref "TFT1") (pin "32") (pinfunction "DB0_32") (pintype "bidirectional"))
    )
    (net (code "61") (name "Net-(U1-PTA18)") (class "Default")
      (node (ref "U1") (pin "32") (pinfunction "PTA18_32") (pintype "bidirectional"))
      (node (ref "Y2") (pin "3") (pinfunction "2_3") (pintype "passive"))
    )
    (net (code "62") (name "Net-(U1-PTA19)") (class "Default")
      (node (ref "U1") (pin "33") (pinfunction "PTA19_33") (pintype "bidirectional"))
      (node (ref "Y2") (pin "1") (pinfunction "1_1") (pintype "passive"))
    )
    (net (code "63") (name "Net-(U1-PTD6)") (class "Default")
      (node (ref "LED") (pin "A") (pinfunction "A_A") (pintype "passive"))
      (node (ref "U1") (pin "63") (pinfunction "PTD6_63") (pintype "bidirectional"))
    )
    (net (code "64") (name "Net-(U1-PTD7)") (class "Default")
      (node (ref "R14") (pin "1") (pinfunction "1_1") (pintype "passive"))
      (node (ref "U1") (pin "64") (pinfunction "PTD7_64") (pintype "bidirectional"))
    )
    (net (code "65") (name "Net-(U1-VDDA)") (class "Default")
      (node (ref "C5") (pin "1") (pinfunction "1_1") (pintype "passive"))
      (node (ref "L2") (pin "1") (pinfunction "1_1") (pintype "passive"))
      (node (ref "R1") (pin "1") (pinfunction "1_1") (pintype "passive"))
      (node (ref "U1") (pin "13") (pinfunction "VDDA_13") (pintype "bidirectional"))
    )
    (net (code "66") (name "Net-(U1-VREFH)") (class "Default")
      (node (ref "C6") (pin "1") (pinfunction "1_1") (pintype "passive"))
      (node (ref "R1") (pin "2") (pinfunction "2_2") (pintype "passive"))
      (node (ref "U1") (pin "14") (pinfunction "VREFH_14") (pintype "bidirectional"))
    )
    (net (code "67") (name "Net-(U1-VREFL)") (class "Default")
      (node (ref "C5") (pin "2") (pinfunction "2_2") (pintype "passive"))
      (node (ref "C6") (pin "2") (pinfunction "2_2") (pintype "passive"))
      (node (ref "C7") (pin "2") (pinfunction "2_2") (pintype "passive"))
      (node (ref "L1") (pin "2") (pinfunction "2_2") (pintype "passive"))
      (node (ref "U1") (pin "15") (pinfunction "VREFL_15") (pintype "bidirectional"))
      (node (ref "U1") (pin "16") (pinfunction "VSSA_16") (pintype "bidirectional"))
    )
    (net (code "68") (name "Net-(U1-VREF_OUT)") (class "Default")
      (node (ref "C7") (pin "1") (pinfunction "1_1") (pintype "passive"))
      (node (ref "U1") (pin "17") (pinfunction "VREF_OUT_17") (pintype "bidirectional"))
    )
    (net (code "69") (name "Net-(X1-CH_PD)") (class "Default")
      (node (ref "R4") (pin "1") (pinfunction "1_1") (pintype "passive"))
      (node (ref "X1") (pin "3") (pinfunction "CH_PD_3") (pintype "input"))
    )
    (net (code "70") (name "Net-(X1-GPIO2)") (class "Default")
      (node (ref "R3") (pin "1") (pinfunction "1_1") (pintype "passive"))
      (node (ref "X1") (pin "11") (pinfunction "GPIO2_11") (pintype "bidirectional"))
    )
    (net (code "71") (name "VCC") (class "Default")
      (node (ref "C11") (pin "1") (pinfunction "1_1") (pintype "passive"))
      (node (ref "D1") (pin "3") (pinfunction "C_3") (pintype "passive"))
      (node (ref "FTDI") (pin "4") (pinfunction "4_4") (pintype "passive"))
      (node (ref "U2") (pin "3") (pinfunction "IN_3") (pintype "input"))
    )
    (net (code "72") (name "unconnected-(J1B-DATA1-Pad8)") (class "Default")
      (node (ref "J1") (pin "8") (pinfunction "DATA1_8") (pintype "bidirectional"))
    )
    (net (code "73") (name "unconnected-(J1B-DATA2-Pad1)") (class "Default")
      (node (ref "J1") (pin "1") (pinfunction "DATA2_1") (pintype "bidirectional"))
    )
    (net (code "74") (name "unconnected-(TFT1-#RD-Pad35)") (class "Default")
      (node (ref "TFT1") (pin "35") (pinfunction "#RD_35") (pintype "bidirectional"))
    )
    (net (code "75") (name "unconnected-(TFT1-DE-Pad14)") (class "Default")
      (node (ref "TFT1") (pin "14") (pinfunction "DE_14") (pintype "bidirectional"))
    )
    (net (code "76") (name "unconnected-(TFT1-DOTCLK-Pad13)") (class "Default")
      (node (ref "TFT1") (pin "13") (pinfunction "DOTCLK_13") (pintype "bidirectional"))
    )
    (net (code "77") (name "unconnected-(TFT1-HSYNC-Pad12)") (class "Default")
      (node (ref "TFT1") (pin "12") (pinfunction "HSYNC_12") (pintype "bidirectional"))
    )
    (net (code "78") (name "unconnected-(TFT1-TE-Pad39)") (class "Default")
      (node (ref "TFT1") (pin "39") (pinfunction "TE_39") (pintype "bidirectional"))
    )
    (net (code "79") (name "unconnected-(TFT1-VSYNC-Pad11)") (class "Default")
      (node (ref "TFT1") (pin "11") (pinfunction "VSYNC_11") (pintype "bidirectional"))
    )
    (net (code "80") (name "unconnected-(TFT1-XL-Pad46)") (class "Default")
      (node (ref "TFT1") (pin "46") (pinfunction "XL_46") (pintype "bidirectional"))
    )
    (net (code "81") (name "unconnected-(TFT1-XR-Pad44)") (class "Default")
      (node (ref "TFT1") (pin "44") (pinfunction "XR_44") (pintype "bidirectional"))
    )
    (net (code "82") (name "unconnected-(TFT1-YD-Pad45)") (class "Default")
      (node (ref "TFT1") (pin "45") (pinfunction "YD_45") (pintype "bidirectional"))
    )
    (net (code "83") (name "unconnected-(TFT1-YU-Pad47)") (class "Default")
      (node (ref "TFT1") (pin "47") (pinfunction "YU_47") (pintype "bidirectional"))
    )
    (net (code "84") (name "unconnected-(U1-ADC0_DM0-Pad10)") (class "Default")
      (node (ref "U1") (pin "10") (pinfunction "ADC0_DM0_10") (pintype "bidirectional"))
    )
    (net (code "85") (name "unconnected-(U1-ADC0_DM3-Pad12)") (class "Default")
      (node (ref "U1") (pin "12") (pinfunction "ADC0_DM3_12") (pintype "bidirectional"))
    )
    (net (code "86") (name "unconnected-(U1-ADC0_DP0-Pad9)") (class "Default")
      (node (ref "U1") (pin "9") (pinfunction "ADC0_DP0_9") (pintype "bidirectional"))
    )
    (net (code "87") (name "unconnected-(U1-ADC0_DP3-Pad11)") (class "Default")
      (node (ref "U1") (pin "11") (pinfunction "ADC0_DP3_11") (pintype "bidirectional"))
    )
    (net (code "88") (name "unconnected-(U1-DAC0-Pad18)") (class "Default")
      (node (ref "U1") (pin "18") (pinfunction "DAC0_18") (pintype "bidirectional"))
    )
    (net (code "89") (name "unconnected-(U1-EXTAL32-Pad20)") (class "Default")
      (node (ref "U1") (pin "20") (pinfunction "EXTAL32_20") (pintype "bidirectional"))
    )
    (net (code "90") (name "unconnected-(U1-PTA5-Pad27)") (class "Default")
      (node (ref "U1") (pin "27") (pinfunction "PTA5_27") (pintype "bidirectional"))
    )
    (net (code "91") (name "unconnected-(U1-PTB19-Pad42)") (class "Default")
      (node (ref "U1") (pin "42") (pinfunction "PTB19_42") (pintype "bidirectional"))
    )
    (net (code "92") (name "unconnected-(U1-PTC2-Pad45)") (class "Default")
      (node (ref "U1") (pin "45") (pinfunction "PTC2_45") (pintype "bidirectional"))
    )
    (net (code "93") (name "unconnected-(U1-PTC10-Pad55)") (class "Default")
      (node (ref "U1") (pin "55") (pinfunction "PTC10_55") (pintype "bidirectional"))
    )
    (net (code "94") (name "unconnected-(U1-PTC11-Pad56)") (class "Default")
      (node (ref "U1") (pin "56") (pinfunction "PTC11_56") (pintype "bidirectional"))
    )
    (net (code "95") (name "unconnected-(U1-PTE0-Pad1)") (class "Default")
      (node (ref "U1") (pin "1") (pinfunction "PTE0_1") (pintype "bidirectional"))
    )
    (net (code "96") (name "unconnected-(U1-PTE1-Pad2)") (class "Default")
      (node (ref "U1") (pin "2") (pinfunction "PTE1_2") (pintype "bidirectional"))
    )
    (net (code "97") (name "unconnected-(U1-VREGIN-Pad8)") (class "Default")
      (node (ref "U1") (pin "8") (pinfunction "VREGIN_8") (pintype "bidirectional"))
    )
    (net (code "98") (name "unconnected-(U1-XTAL32-Pad19)") (class "Default")
      (node (ref "U1") (pin "19") (pinfunction "XTAL32_19") (pintype "bidirectional"))
    )
    (net (code "99") (name "unconnected-(U4-PTA0-Pad14)") (class "Default")
      (node (ref "U4") (pin "14") (pinfunction "PTA0_14") (pintype "bidirectional"))
    )
    (net (code "100") (name "unconnected-(U4-PTA1-Pad15)") (class "Default")
      (node (ref "U4") (pin "15") (pinfunction "PTA1_15") (pintype "bidirectional"))
    )
    (net (code "101") (name "unconnected-(U4-PTA2-Pad16)") (class "Default")
      (node (ref "U4") (pin "16") (pinfunction "PTA2_16") (pintype "bidirectional"))
    )
    (net (code "102") (name "unconnected-(U4-PTA3-Pad3)") (class "Default")
      (node (ref "U4") (pin "3") (pinfunction "PTA3_3") (pintype "bidirectional"))
    )
    (net (code "103") (name "unconnected-(U4-PTA5-Pad5)") (class "Default")
      (node (ref "U4") (pin "5") (pinfunction "PTA5_5") (pintype "bidirectional"))
    )
    (net (code "104") (name "unconnected-(U4-PTB3-Pad11)") (class "Default")
      (node (ref "U4") (pin "11") (pinfunction "PTB3_11") (pintype "bidirectional"))
    )
    (net (code "105") (name "unconnected-(U4-PTB4-Pad12)") (class "Default")
      (node (ref "U4") (pin "12") (pinfunction "PTB4_12") (pintype "bidirectional"))
    )
    (net (code "106") (name "unconnected-(X1-ADC-Pad2)") (class "Default")
      (node (ref "X1") (pin "2") (pinfunction "ADC_2") (pintype "passive"))
    )
  )
)
